# 3_-_STM32F103_Debugger.net
KiCad netlist of a schematic drawn in Altium Designer
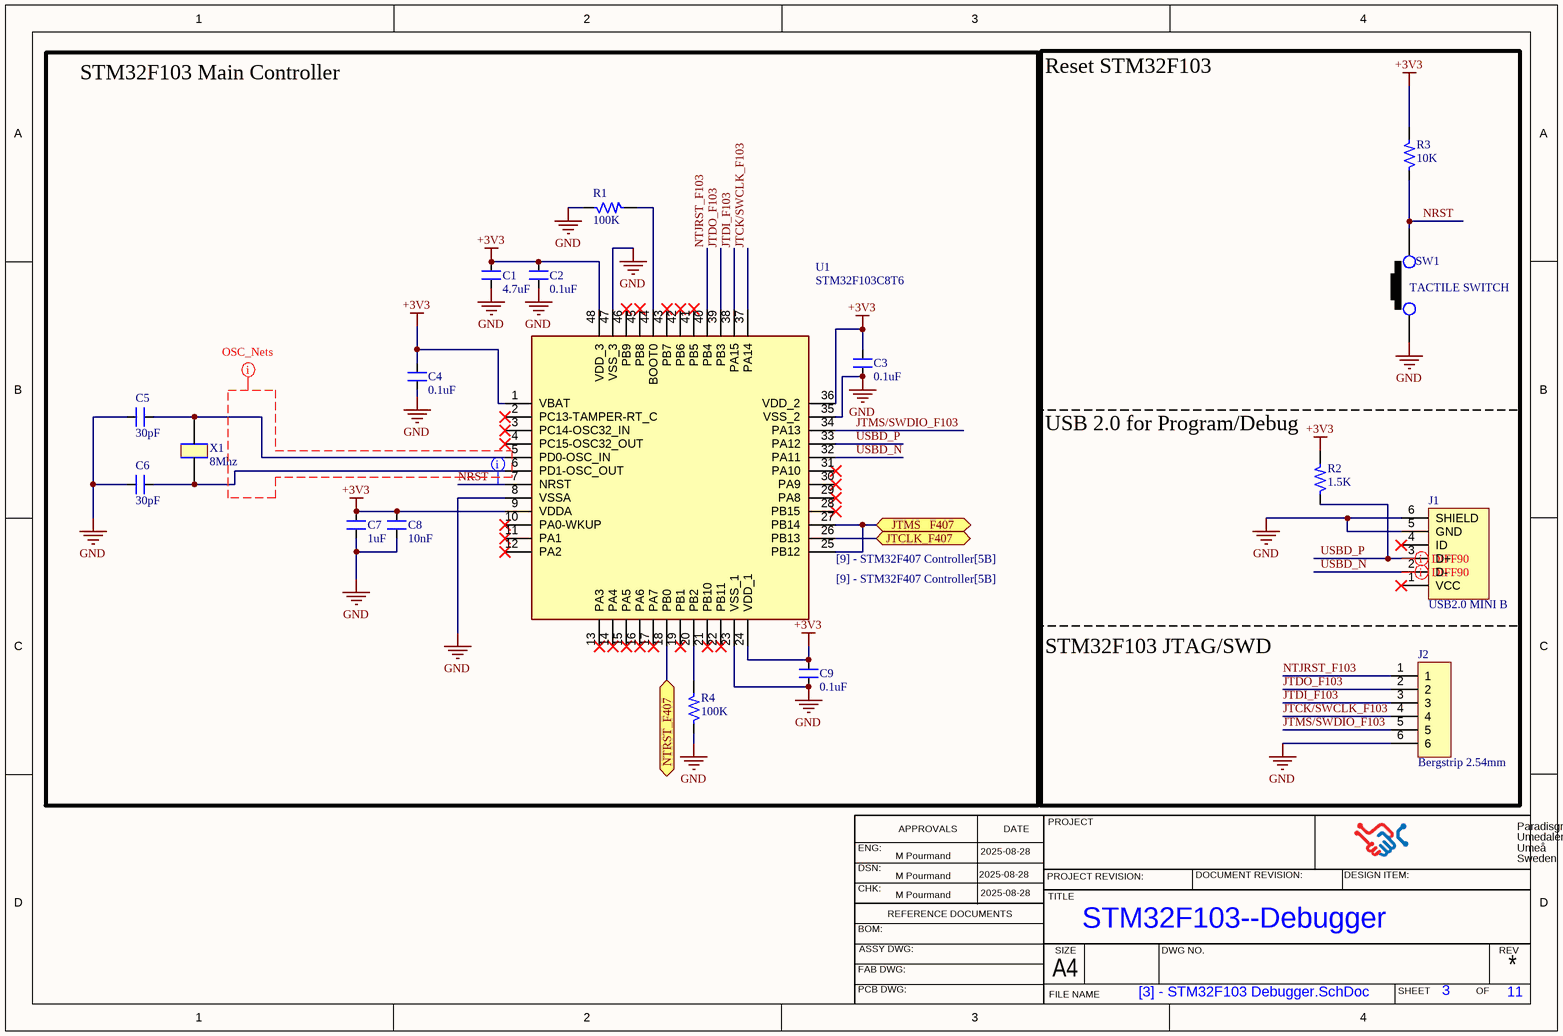
[diagram p0: [3] - STM32F103 Debugger.SchDoc]

(export (version "E")
  (design (tool "Eeschema 10.0.6"))
  (components
    (comp (ref "C1")
      (value "4.7uF")
      (footprint "CAP_0805")
      (description "4.7µF ±10% 50V Ceramic Capacitor X5R 0805 (2012 Metric)")
      (fields
        (field (name "MANUFACTURER") "Yageo")
        (field (name "MANUFACTURER PART NUMBER") "GRM21BR61H475KE51L")
      )
      (libsource (lib "ESTEEMPCBLIB") (part "CAP_4.7uF-50V-10%-0805"))
    )
    (comp (ref "C2")
      (value "0.1uF")
      (footprint "CAP_0805")
      (description "0.1µF ±10% 50V Ceramic Capacitor X7R 0805 (2012 Metric)")
      (fields
        (field (name "MANUFACTURER") "Samsung")
        (field (name "MANUFACTURER PART NUMBER") "CL21B104KBCNNNC")
      )
      (libsource (lib "ESTEEMPCBLIB") (part "CAP_0.1uF-50V-10%-0805"))
    )
    (comp (ref "C3")
      (value "0.1uF")
      (footprint "CAP_0805")
      (description "0.1µF ±10% 50V Ceramic Capacitor X7R 0805 (2012 Metric)")
      (fields
        (field (name "MANUFACTURER") "Samsung")
        (field (name "MANUFACTURER PART NUMBER") "CL21B104KBCNNNC")
      )
      (libsource (lib "ESTEEMPCBLIB") (part "CAP_0.1uF-50V-10%-0805"))
    )
    (comp (ref "C4")
      (value "0.1uF")
      (footprint "CAP_0805")
      (description "0.1µF ±10% 50V Ceramic Capacitor X7R 0805 (2012 Metric)")
      (fields
        (field (name "MANUFACTURER") "Samsung")
        (field (name "MANUFACTURER PART NUMBER") "CL21B104KBCNNNC")
      )
      (libsource (lib "ESTEEMPCBLIB") (part "CAP_0.1uF-50V-10%-0805"))
    )
    (comp (ref "C5")
      (value "30pF")
      (footprint "CAP_0805")
      (description "±10% 50V Ceramic Capacitor C0G, NP0 0805 (2012 Metric)")
      (fields
        (field (name "MANUFACTURER PART NUMBER") "C0805C300K5GAC7800")
        (field (name "MANUFACTURER") "KEMET")
      )
      (libsource (lib "ESTEEMPCBLIB") (part "CAP_30pF-50V-10%-0805"))
    )
    (comp (ref "C6")
      (value "30pF")
      (footprint "CAP_0805")
      (description "±10% 50V Ceramic Capacitor C0G, NP0 0805 (2012 Metric)")
      (fields
        (field (name "MANUFACTURER PART NUMBER") "C0805C300K5GAC7800")
        (field (name "MANUFACTURER") "KEMET")
      )
      (libsource (lib "ESTEEMPCBLIB") (part "CAP_30pF-50V-10%-0805"))
    )
    (comp (ref "C7")
      (value "1uF")
      (footprint "CAP_0805")
      (description "1µF ±5% 50V Ceramic Capacitor X7R 0805 (2012 Metric)")
      (fields
        (field (name "MANUFACTURER") "Samsung")
        (field (name "MANUFACTURER PART NUMBER") "CC0805JKX7R9BB105")
      )
      (libsource (lib "ESTEEMPCBLIB") (part "CAP_1uF-50V-5%-0805"))
    )
    (comp (ref "C8")
      (value "10nF")
      (footprint "CAP_0805")
      (description "10000pF ±10% 50V Ceramic Capacitor X7R 0805 (2012 Metric)")
      (fields
        (field (name "MANUFACTURER") "Samsung")
        (field (name "MANUFACTURER PART NUMBER") "C0805C103K5RECAUTO")
      )
      (libsource (lib "ESTEEMPCBLIB") (part "CAP_10nF-50V-10%-0805"))
    )
    (comp (ref "C9")
      (value "0.1uF")
      (footprint "CAP_0805")
      (description "0.1µF ±10% 50V Ceramic Capacitor X7R 0805 (2012 Metric)")
      (fields
        (field (name "MANUFACTURER") "Samsung")
        (field (name "MANUFACTURER PART NUMBER") "CL21B104KBCNNNC")
      )
      (libsource (lib "ESTEEMPCBLIB") (part "CAP_0.1uF-50V-10%-0805"))
    )
    (comp (ref "J1")
      (value "USB2.0 MINI B")
      (footprint "CON_690-005-299-043")
      (description "USB - mini B USB 2.0 Receptacle Connector 5 Position Surface Mount, Right Angle")
      (fields
        (field (name "MANUFACTURER") "EDAC")
        (field (name "MANUFACTURER PART NUMBER") "690-005-299-043")
      )
      (libsource (lib "ESTEEMPCBLIB") (part "CON_USB2.0-MINIB-SMD"))
    )
    (comp (ref "J2")
      (value "Bergstrip 2.54mm")
      (footprint "CON6_100_59D78_TH_ST")
      (description "6 Pins, 1 Row 2.54mm Pitch, Straight bergstrip, Female")
      (fields (field (name "MANUFACTURER") "Molex") (field (name "MANUFACTURER PART NUMBER") "22-10-2061"))
      (libsource (lib "ESTEEMPCBLIB") (part "CON-BS-SKT_6X1-100-ST-TH"))
    )
    (comp (ref "R1")
      (value "100K")
      (footprint "RES_0603")
      (description "100 kOhms ±1% 0.1W, 1/10W Chip Resistor 0603 (1608 Metric) Automotive AEC-Q200 Thick Film")
      (fields
        (field (name "MANUFACTURER") "Stackpole Electronics")
        (field (name "MANUFACTURER PART NUMBER") "RMCF0603FT100K")
      )
      (libsource (lib "ESTEEMPCBLIB") (part "RES_100K-0.1W-1%-0603"))
    )
    (comp (ref "R2")
      (value "1.5K")
      (footprint "RES_0805")
      (description "1.5 kOhms ±1% 0.125W, 1/8W Chip Resistor 0805 (2012 Metric) Thick Film")
      (fields
        (field (name "MANUFACTURER") "TE Connectivity Passive Product")
        (field (name "MANUFACTURER PART NUMBER") "CRG0805F1K5")
      )
      (libsource (lib "ESTEEMPCBLIB") (part "RES_1.5K-0.125W-1%-0805"))
    )
    (comp (ref "R3")
      (value "10K")
      (footprint "RES_0603")
      (description "10 kOhms ±1% 0.1W, 1/10W Chip Resistor 0603 (1608 Metric) Automotive AEC-Q200 Thick Film")
      (fields (field (name "MANUFACTURER") "Walsin") (field (name "MANUFACTURER PART NUMBER") "WR06X1002FTL"))
      (libsource (lib "ESTEEMPCBLIB") (part "RES_10K-0.1W-1%-0603"))
    )
    (comp (ref "R4")
      (value "100K")
      (footprint "RES_0603")
      (description "100 kOhms ±1% 0.1W, 1/10W Chip Resistor 0603 (1608 Metric) Automotive AEC-Q200 Thick Film")
      (fields
        (field (name "MANUFACTURER") "Stackpole Electronics")
        (field (name "MANUFACTURER PART NUMBER") "RMCF0603FT100K")
      )
      (libsource (lib "ESTEEMPCBLIB") (part "RES_100K-0.1W-1%-0603"))
    )
    (comp (ref "SW1")
      (value "TACTILE SWITCH")
      (footprint "SW_342_SMD")
      (description "Tactile Switch SPST-NO Top Actuated Surface Mount")
      (fields
        (field (name "MANUFACTURER") "ITT C&K")
        (field (name "MANUFACTURER PART NUMBER") "RS-282G05A3-SMRT")
      )
      (libsource (lib "ESTEEMPCBLIB") (part "SW1_RS-282G05A3-SMRT-SMD"))
    )
    (comp (ref "U1")
      (value "STM32F103C8T6")
      (footprint "LQFP-48_19.6_393_58X11_SMD")
      (description "ARM® Cortex®-M3 STM32F1 Microcontroller IC 32-Bit 72MHz 64KB (64K x 8) FLASH 48-LQFP (7x7)")
      (fields (field (name "MANUFACTURER") "STMicroelectronics"))
      (libsource (lib "ESTEEMPCBLIB") (part "IC_STM32F103C8T6"))
    )
    (comp (ref "X1")
      (value "8Mhz")
      (footprint "XTAL_314_240X47_SMD")
      (description "8MHz ±30ppm Crystal 32pF 60 Ohms HC-49/US")
      (fields
        (field (name "MANUFACTURER") "Fox Electronics")
        (field (name "MANUFACTURER PART NUMBER") "ECS-80-32-5PX-TR")
      )
      (libsource (lib "ESTEEMPCBLIB") (part "XTAL_8MHZ-ECS-80-32-5PX-SMD"))
    )
  )
  (nets
    (net (code "1") (name "+3V3") (class "Default")
      (node (ref "C1") (pin "2") (pinfunction "2_2") (pintype "passive"))
      (node (ref "C2") (pin "2") (pinfunction "2_2") (pintype "passive"))
      (node (ref "C3") (pin "2") (pinfunction "2_2") (pintype "passive"))
      (node (ref "C4") (pin "2") (pinfunction "2_2") (pintype "passive"))
      (node (ref "C7") (pin "2") (pinfunction "2_2") (pintype "passive"))
      (node (ref "C8") (pin "2") (pinfunction "2_2") (pintype "passive"))
      (node (ref "C9") (pin "2") (pinfunction "2_2") (pintype "passive"))
      (node (ref "R2") (pin "2") (pinfunction "2_2") (pintype "passive"))
      (node (ref "R3") (pin "2") (pinfunction "2_2") (pintype "passive"))
      (node (ref "U1") (pin "1") (pinfunction "VBAT_1") (pintype "passive"))
      (node (ref "U1") (pin "24") (pinfunction "VDD_1_24") (pintype "passive"))
      (node (ref "U1") (pin "36") (pinfunction "VDD_2_36") (pintype "passive"))
      (node (ref "U1") (pin "48") (pinfunction "VDD_3_48") (pintype "passive"))
      (node (ref "U1") (pin "9") (pinfunction "VDDA_9") (pintype "passive"))
    )
    (net (code "2") (name "/JTCK{slash}SWCLK_F103") (class "Default")
      (node (ref "J2") (pin "4") (pinfunction "4_4") (pintype "passive"))
      (node (ref "U1") (pin "37") (pinfunction "PA14_37") (pintype "passive"))
    )
    (net (code "3") (name "/JTCLK_F407") (class "Default")
      (node (ref "U1") (pin "26") (pinfunction "PB13_26") (pintype "passive"))
    )
    (net (code "4") (name "/JTDI_F103") (class "Default")
      (node (ref "J2") (pin "3") (pinfunction "3_3") (pintype "passive"))
      (node (ref "U1") (pin "38") (pinfunction "PA15_38") (pintype "passive"))
    )
    (net (code "5") (name "/JTDO_F103") (class "Default")
      (node (ref "J2") (pin "2") (pinfunction "2_2") (pintype "passive"))
      (node (ref "U1") (pin "39") (pinfunction "PB3_39") (pintype "passive"))
    )
    (net (code "6") (name "/JTMS   F407") (class "Default")
      (node (ref "U1") (pin "25") (pinfunction "PB12_25") (pintype "passive"))
      (node (ref "U1") (pin "27") (pinfunction "PB14_27") (pintype "passive"))
    )
    (net (code "7") (name "/JTMS{slash}SWDIO_F103") (class "Default")
      (node (ref "J2") (pin "5") (pinfunction "5_5") (pintype "passive"))
      (node (ref "U1") (pin "34") (pinfunction "PA13_34") (pintype "passive"))
    )
    (net (code "8") (name "/NRST") (class "Default")
      (node (ref "R3") (pin "1") (pinfunction "1_1") (pintype "passive"))
      (node (ref "SW1") (pin "2") (pinfunction "2_2") (pintype "passive"))
      (node (ref "U1") (pin "7") (pinfunction "NRST_7") (pintype "passive"))
    )
    (net (code "9") (name "/NTJRST_F103") (class "Default")
      (node (ref "J2") (pin "1") (pinfunction "1_1") (pintype "passive"))
      (node (ref "U1") (pin "40") (pinfunction "PB4_40") (pintype "passive"))
    )
    (net (code "10") (name "/NTRST_F407") (class "Default")
      (node (ref "U1") (pin "18") (pinfunction "PB0_18") (pintype "passive"))
    )
    (net (code "11") (name "/USBD_N") (class "Default")
      (node (ref "J1") (pin "2") (pinfunction "D-_2") (pintype "passive"))
      (node (ref "U1") (pin "32") (pinfunction "PA11_32") (pintype "passive"))
    )
    (net (code "12") (name "/USBD_P") (class "Default")
      (node (ref "J1") (pin "3") (pinfunction "D+_3") (pintype "passive"))
      (node (ref "R2") (pin "1") (pinfunction "1_1") (pintype "passive"))
      (node (ref "U1") (pin "33") (pinfunction "PA12_33") (pintype "passive"))
    )
    (net (code "13") (name "GND") (class "Default")
      (node (ref "C1") (pin "1") (pinfunction "1_1") (pintype "passive"))
      (node (ref "C2") (pin "1") (pinfunction "1_1") (pintype "passive"))
      (node (ref "C3") (pin "1") (pinfunction "1_1") (pintype "passive"))
      (node (ref "C4") (pin "1") (pinfunction "1_1") (pintype "passive"))
      (node (ref "C5") (pin "1") (pinfunction "1_1") (pintype "passive"))
      (node (ref "C6") (pin "1") (pinfunction "1_1") (pintype "passive"))
      (node (ref "C7") (pin "1") (pinfunction "1_1") (pintype "passive"))
      (node (ref "C8") (pin "1") (pinfunction "1_1") (pintype "passive"))
      (node (ref "C9") (pin "1") (pinfunction "1_1") (pintype "passive"))
      (node (ref "J1") (pin "5") (pinfunction "GND_5") (pintype "passive"))
      (node (ref "J1") (pin "6") (pinfunction "SHIELD_6") (pintype "passive"))
      (node (ref "J2") (pin "6") (pinfunction "6_6") (pintype "passive"))
      (node (ref "R1") (pin "1") (pinfunction "1_1") (pintype "passive"))
      (node (ref "R4") (pin "1") (pinfunction "1_1") (pintype "passive"))
      (node (ref "SW1") (pin "1") (pinfunction "1_1") (pintype "passive"))
      (node (ref "U1") (pin "23") (pinfunction "VSS_1_23") (pintype "passive"))
      (node (ref "U1") (pin "35") (pinfunction "VSS_2_35") (pintype "passive"))
      (node (ref "U1") (pin "47") (pinfunction "VSS_3_47") (pintype "passive"))
      (node (ref "U1") (pin "8") (pinfunction "VSSA_8") (pintype "passive"))
    )
    (net (code "14") (name "Net-(U1-BOOT0)") (class "Default")
      (node (ref "R1") (pin "2") (pinfunction "2_2") (pintype "passive"))
      (node (ref "U1") (pin "44") (pinfunction "BOOT0_44") (pintype "passive"))
    )
    (net (code "15") (name "Net-(U1-PB2)") (class "Default")
      (node (ref "R4") (pin "2") (pinfunction "2_2") (pintype "passive"))
      (node (ref "U1") (pin "20") (pinfunction "PB2_20") (pintype "passive"))
    )
    (net (code "16") (name "Net-(U1-PD0-OSC_IN)") (class "Default")
      (node (ref "C5") (pin "2") (pinfunction "2_2") (pintype "passive"))
      (node (ref "U1") (pin "5") (pinfunction "PD0-OSC_IN_5") (pintype "passive"))
      (node (ref "X1") (pin "2") (pinfunction "2_2") (pintype "passive"))
    )
    (net (code "17") (name "Net-(U1-PD1-OSC_OUT)") (class "Default")
      (node (ref "C6") (pin "2") (pinfunction "2_2") (pintype "passive"))
      (node (ref "U1") (pin "6") (pinfunction "PD1-OSC_OUT_6") (pintype "passive"))
      (node (ref "X1") (pin "1") (pinfunction "1_1") (pintype "passive"))
    )
    (net (code "18") (name "unconnected-(J1-ID-Pad4)") (class "Default")
      (node (ref "J1") (pin "4") (pinfunction "ID_4") (pintype "passive+no_connect"))
    )
    (net (code "19") (name "unconnected-(J1-VCC-Pad1)") (class "Default")
      (node (ref "J1") (pin "1") (pinfunction "VCC_1") (pintype "passive+no_connect"))
    )
    (net (code "20") (name "unconnected-(U1-PA0-WKUP-Pad10)") (class "Default")
      (node (ref "U1") (pin "10") (pinfunction "PA0-WKUP_10") (pintype "passive+no_connect"))
    )
    (net (code "21") (name "unconnected-(U1-PA1-Pad11)") (class "Default")
      (node (ref "U1") (pin "11") (pinfunction "PA1_11") (pintype "passive+no_connect"))
    )
    (net (code "22") (name "unconnected-(U1-PA2-Pad12)") (class "Default")
      (node (ref "U1") (pin "12") (pinfunction "PA2_12") (pintype "passive+no_connect"))
    )
    (net (code "23") (name "unconnected-(U1-PA3-Pad13)") (class "Default")
      (node (ref "U1") (pin "13") (pinfunction "PA3_13") (pintype "passive+no_connect"))
    )
    (net (code "24") (name "unconnected-(U1-PA4-Pad14)") (class "Default")
      (node (ref "U1") (pin "14") (pinfunction "PA4_14") (pintype "passive+no_connect"))
    )
    (net (code "25") (name "unconnected-(U1-PA5-Pad15)") (class "Default")
      (node (ref "U1") (pin "15") (pinfunction "PA5_15") (pintype "passive+no_connect"))
    )
    (net (code "26") (name "unconnected-(U1-PA6-Pad16)") (class "Default")
      (node (ref "U1") (pin "16") (pinfunction "PA6_16") (pintype "passive+no_connect"))
    )
    (net (code "27") (name "unconnected-(U1-PA7-Pad17)") (class "Default")
      (node (ref "U1") (pin "17") (pinfunction "PA7_17") (pintype "passive+no_connect"))
    )
    (net (code "28") (name "unconnected-(U1-PA8-Pad29)") (class "Default")
      (node (ref "U1") (pin "29") (pinfunction "PA8_29") (pintype "passive+no_connect"))
    )
    (net (code "29") (name "unconnected-(U1-PA9-Pad30)") (class "Default")
      (node (ref "U1") (pin "30") (pinfunction "PA9_30") (pintype "passive+no_connect"))
    )
    (net (code "30") (name "unconnected-(U1-PA10-Pad31)") (class "Default")
      (node (ref "U1") (pin "31") (pinfunction "PA10_31") (pintype "passive+no_connect"))
    )
    (net (code "31") (name "unconnected-(U1-PB1-Pad19)") (class "Default")
      (node (ref "U1") (pin "19") (pinfunction "PB1_19") (pintype "passive+no_connect"))
    )
    (net (code "32") (name "unconnected-(U1-PB5-Pad41)") (class "Default")
      (node (ref "U1") (pin "41") (pinfunction "PB5_41") (pintype "passive+no_connect"))
    )
    (net (code "33") (name "unconnected-(U1-PB6-Pad42)") (class "Default")
      (node (ref "U1") (pin "42") (pinfunction "PB6_42") (pintype "passive+no_connect"))
    )
    (net (code "34") (name "unconnected-(U1-PB7-Pad43)") (class "Default")
      (node (ref "U1") (pin "43") (pinfunction "PB7_43") (pintype "passive+no_connect"))
    )
    (net (code "35") (name "unconnected-(U1-PB8-Pad45)") (class "Default")
      (node (ref "U1") (pin "45") (pinfunction "PB8_45") (pintype "passive+no_connect"))
    )
    (net (code "36") (name "unconnected-(U1-PB9-Pad46)") (class "Default")
      (node (ref "U1") (pin "46") (pinfunction "PB9_46") (pintype "passive+no_connect"))
    )
    (net (code "37") (name "unconnected-(U1-PB10-Pad21)") (class "Default")
      (node (ref "U1") (pin "21") (pinfunction "PB10_21") (pintype "passive+no_connect"))
    )
    (net (code "38") (name "unconnected-(U1-PB11-Pad22)") (class "Default")
      (node (ref "U1") (pin "22") (pinfunction "PB11_22") (pintype "passive+no_connect"))
    )
    (net (code "39") (name "unconnected-(U1-PB15-Pad28)") (class "Default")
      (node (ref "U1") (pin "28") (pinfunction "PB15_28") (pintype "passive+no_connect"))
    )
    (net (code "40") (name "unconnected-(U1-PC13-TAMPER-RT_C-Pad2)") (class "Default")
      (node (ref "U1") (pin "2") (pinfunction "PC13-TAMPER-RT_C_2") (pintype "passive+no_connect"))
    )
    (net (code "41") (name "unconnected-(U1-PC14-OSC32_IN-Pad3)") (class "Default")
      (node (ref "U1") (pin "3") (pinfunction "PC14-OSC32_IN_3") (pintype "passive+no_connect"))
    )
    (net (code "42") (name "unconnected-(U1-PC15-OSC32_OUT-Pad4)") (class "Default")
      (node (ref "U1") (pin "4") (pinfunction "PC15-OSC32_OUT_4") (pintype "passive+no_connect"))
    )
  )
)
